# Reference_voltage.net
KiCad netlist of a schematic drawn in Altium Designer
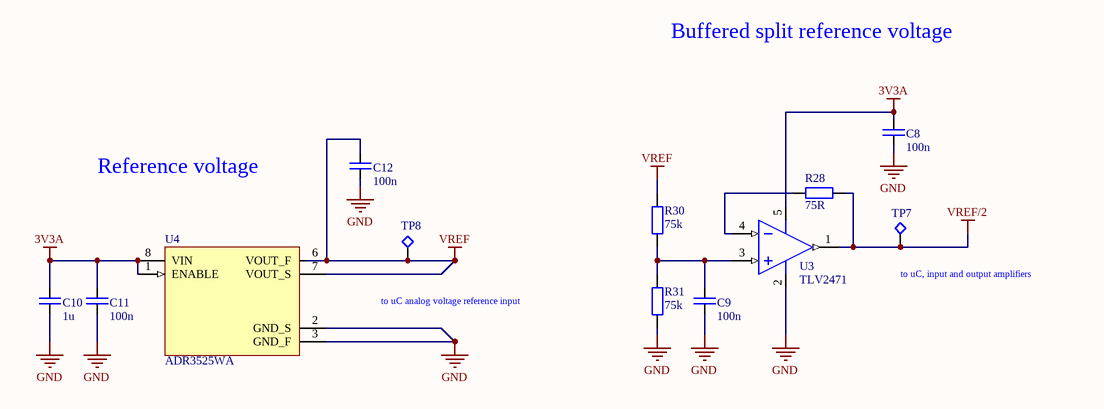
[diagram p0: Reference_voltage.SchDoc]

(export (version "E")
  (design (tool "Eeschema 10.0.6"))
  (components
    (comp (ref "C8")
      (value "100n")
      (footprint "C_0603")
      (description "Generic capacitor")
      (libsource (lib "DAQ_REV_B") (part "Capacitor"))
    )
    (comp (ref "C9")
      (value "100n")
      (footprint "C_0603")
      (description "Generic capacitor")
      (libsource (lib "DAQ_REV_B") (part "Capacitor"))
    )
    (comp (ref "C10")
      (value "1u")
      (footprint "C_0603")
      (description "Generic capacitor")
      (libsource (lib "DAQ_REV_B") (part "Capacitor"))
    )
    (comp (ref "C11")
      (value "100n")
      (footprint "C_0603")
      (description "Generic capacitor")
      (libsource (lib "DAQ_REV_B") (part "Capacitor"))
    )
    (comp (ref "C12")
      (value "100n")
      (footprint "C_0603")
      (description "Generic capacitor")
      (libsource (lib "DAQ_REV_B") (part "Capacitor"))
    )
    (comp (ref "R28")
      (value "75R")
      (footprint "R_0603")
      (description "Generic resistor")
      (libsource (lib "DAQ_REV_B") (part "Resistor"))
    )
    (comp (ref "R30")
      (value "75k")
      (footprint "R_0603")
      (description "Generic resistor")
      (libsource (lib "DAQ_REV_B") (part "Resistor"))
    )
    (comp (ref "R31")
      (value "75k")
      (footprint "R_0603")
      (description "Generic resistor")
      (libsource (lib "DAQ_REV_B") (part "Resistor"))
    )
    (comp (ref "TP7")
      (value "testpoint")
      (footprint "TP1_FULL")
      (description "testpoint 1.5mm diameter no hole")
      (fields (field (name "PART NUMBER") "XXC0006"))
      (libsource (lib "DAQ_REV_B") (part "Test Point"))
    )
    (comp (ref "TP8")
      (value "testpoint")
      (footprint "TP1_FULL")
      (description "testpoint 1.5mm diameter no hole")
      (fields (field (name "PART NUMBER") "XXC0006"))
      (libsource (lib "DAQ_REV_B") (part "Test Point"))
    )
    (comp (ref "U3")
      (value "TLV2471")
      (footprint "SOT23-5")
      (fields (field (name "PART NUMBER") "XOG0002") (field (name "MANUFACTURER") "Texas Instruments"))
      (libsource (lib "DAQ_REV_B") (part "TLV2471"))
    )
    (comp (ref "U4")
      (value "ADR3525WA")
      (footprint "MSOP8")
      (description "Micropower, High Accuracy\r\nVoltage References")
      (fields (field (name "PART NUMBER") "VRX0002") (field (name "MANUFACTURER") "Analog devices"))
      (libsource (lib "DAQ_REV_B") (part "ADR3525W"))
    )
  )
  (nets
    (net (code "1") (name "3V3A") (class "Default")
      (node (ref "C10") (pin "1") (pinfunction "1_1") (pintype "passive"))
      (node (ref "C11") (pin "1") (pinfunction "1_1") (pintype "passive"))
      (node (ref "C8") (pin "2") (pinfunction "2_2") (pintype "passive"))
      (node (ref "U3") (pin "5") (pinfunction "V+_5") (pintype "power_in"))
      (node (ref "U4") (pin "1") (pinfunction "ENABLE_1") (pintype "input"))
      (node (ref "U4") (pin "8") (pinfunction "VIN_8") (pintype "power_in"))
    )
    (net (code "2") (name "GND") (class "Default")
      (node (ref "C10") (pin "2") (pinfunction "2_2") (pintype "passive"))
      (node (ref "C11") (pin "2") (pinfunction "2_2") (pintype "passive"))
      (node (ref "C12") (pin "2") (pinfunction "2_2") (pintype "passive"))
      (node (ref "C8") (pin "1") (pinfunction "1_1") (pintype "passive"))
      (node (ref "C9") (pin "2") (pinfunction "2_2") (pintype "passive"))
      (node (ref "R31") (pin "1") (pintype "passive"))
      (node (ref "U3") (pin "2") (pinfunction "V-_2") (pintype "power_in"))
      (node (ref "U4") (pin "2") (pinfunction "GND_S_2") (pintype "power_in"))
      (node (ref "U4") (pin "3") (pinfunction "GND_F_3") (pintype "power_in"))
    )
    (net (code "3") (name "Net-(U3-+IN_A)") (class "Default")
      (node (ref "C9") (pin "1") (pinfunction "1_1") (pintype "passive"))
      (node (ref "R30") (pin "1") (pintype "passive"))
      (node (ref "R31") (pin "2") (pintype "passive"))
      (node (ref "U3") (pin "3") (pinfunction "+IN_A_3") (pintype "input"))
    )
    (net (code "4") (name "Net-(U3--IN_A)") (class "Default")
      (node (ref "R28") (pin "1") (pintype "passive"))
      (node (ref "U3") (pin "4") (pinfunction "-IN_A_4") (pintype "input"))
    )
    (net (code "5") (name "VREF") (class "Default")
      (node (ref "C12") (pin "1") (pinfunction "1_1") (pintype "passive"))
      (node (ref "R30") (pin "2") (pintype "passive"))
      (node (ref "TP8") (pin "1") (pinfunction "1_1") (pintype "passive"))
      (node (ref "U4") (pin "6") (pinfunction "VOUT_F_6") (pintype "power_in"))
      (node (ref "U4") (pin "7") (pinfunction "VOUT_S_7") (pintype "power_in"))
    )
    (net (code "6") (name "VREF{slash}2") (class "Default")
      (node (ref "R28") (pin "2") (pintype "passive"))
      (node (ref "TP7") (pin "1") (pinfunction "1_1") (pintype "passive"))
      (node (ref "U3") (pin "1") (pinfunction "OUT_A_1") (pintype "output"))
    )
  )
)
